# Sprite.net
KiCad netlist of a schematic drawn in EAGLE
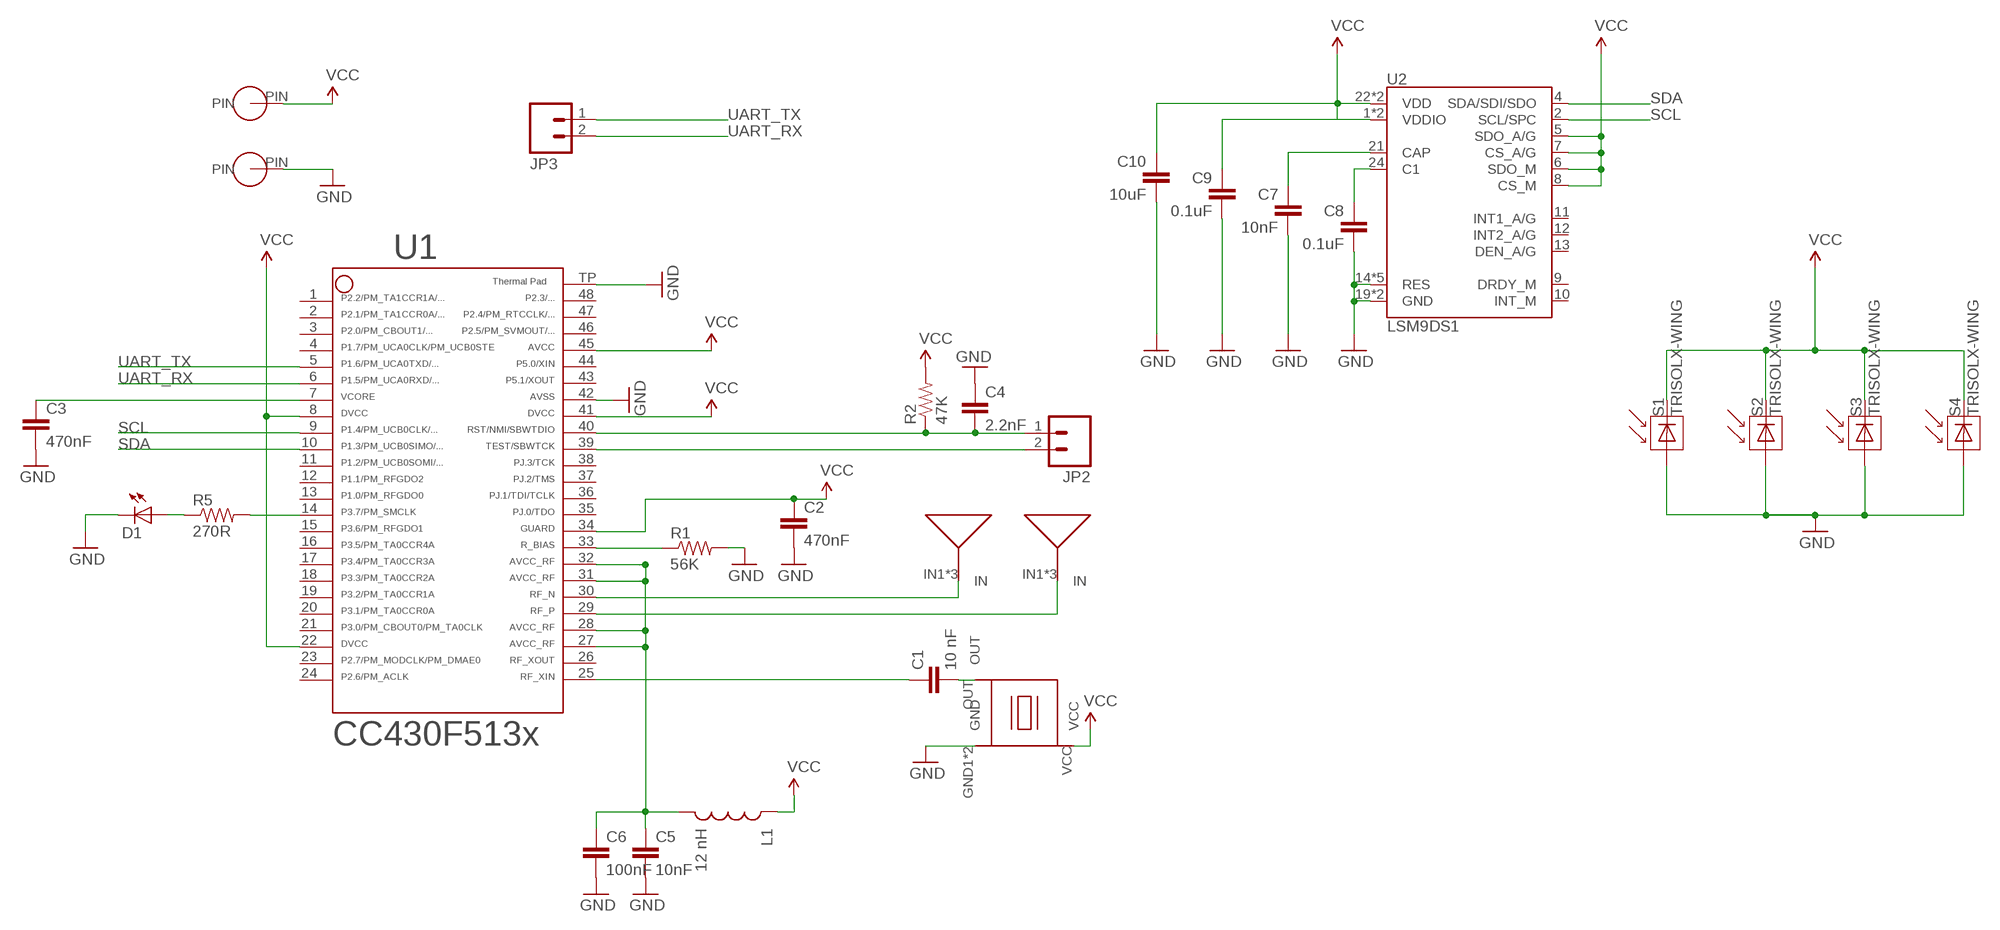
[diagram p0: schematic, sheet 1]

(export (version "E")
  (design (tool "Eeschema 10.0.6"))
  (components
    (comp (ref "ANT-N")
      (value "ANTENNA")
      (footprint "eagle-import:ANTENNA")
      (libsource (lib "eagle-import") (part "ANTENNA"))
    )
    (comp (ref "ANT-P")
      (value "ANTENNA")
      (footprint "eagle-import:ANTENNA")
      (libsource (lib "eagle-import") (part "ANTENNA"))
    )
    (comp (ref "C1")
      (value "10 nF")
      (footprint "eagle-import:0603-CAP")
      (libsource (lib "eagle-import") (part "CAP0603-CAP"))
    )
    (comp (ref "C2")
      (value "470nF")
      (footprint "eagle-import:0603-CAP")
      (libsource (lib "eagle-import") (part "CAP0603-CAP"))
    )
    (comp (ref "C3")
      (value "470nF")
      (footprint "eagle-import:0603-CAP")
      (libsource (lib "eagle-import") (part "CAP0603-CAP"))
    )
    (comp (ref "C4")
      (value "2.2nF")
      (footprint "eagle-import:0603-CAP")
      (libsource (lib "eagle-import") (part "CAP0603-CAP"))
    )
    (comp (ref "C5")
      (value "10nF")
      (footprint "eagle-import:0603-CAP")
      (libsource (lib "eagle-import") (part "CAP0603-CAP"))
    )
    (comp (ref "C6")
      (value "100nF")
      (footprint "eagle-import:0603-CAP")
      (libsource (lib "eagle-import") (part "CAP0603-CAP"))
    )
    (comp (ref "C7")
      (value "10nF")
      (footprint "eagle-import:0603-CAP")
      (libsource (lib "eagle-import") (part "CAP0603-CAP"))
    )
    (comp (ref "C8")
      (value "0.1uF")
      (footprint "eagle-import:0603-CAP")
      (libsource (lib "eagle-import") (part "CAP0603-CAP"))
    )
    (comp (ref "C9")
      (value "0.1uF")
      (footprint "eagle-import:0603-CAP")
      (libsource (lib "eagle-import") (part "CAP0603-CAP"))
    )
    (comp (ref "C10")
      (value "10uF")
      (footprint "eagle-import:0603-CAP")
      (libsource (lib "eagle-import") (part "CAP0603-CAP"))
    )
    (comp (ref "D1")
      (value "LED0603")
      (footprint "eagle-import:LED-0603")
      (libsource (lib "eagle-import") (part "LED0603"))
    )
    (comp (ref "JP2")
      (value "M02PTH")
      (footprint "eagle-import:1X02")
      (libsource (lib "eagle-import") (part "M02PTH"))
    )
    (comp (ref "JP3")
      (value "M02PTH")
      (footprint "eagle-import:1X02")
      (libsource (lib "eagle-import") (part "M02PTH"))
    )
    (comp (ref "L1")
      (value "12 nH")
      (footprint "eagle-import:0603")
      (libsource (lib "eagle-import") (part "INDUCTOR0603"))
    )
    (comp (ref "P1")
      (value "SPRITE_PIN")
      (footprint "eagle-import:SPRITE_PIN")
      (libsource (lib "eagle-import") (part "SPRITE_PIN"))
    )
    (comp (ref "P2")
      (value "SPRITE_PIN")
      (footprint "eagle-import:SPRITE_PIN")
      (libsource (lib "eagle-import") (part "SPRITE_PIN"))
    )
    (comp (ref "R1")
      (value "56K")
      (footprint "eagle-import:0603-RES")
      (libsource (lib "eagle-import") (part "RESISTOR0603-RES"))
    )
    (comp (ref "R2")
      (value "47K")
      (footprint "eagle-import:0603-RES")
      (libsource (lib "eagle-import") (part "RESISTOR0603-RES"))
    )
    (comp (ref "R5")
      (value "270R")
      (footprint "eagle-import:0603-RES")
      (libsource (lib "eagle-import") (part "RESISTOR0603-RES"))
    )
    (comp (ref "S1")
      (value "TRISOLX-WING")
      (footprint "eagle-import:TRISOLX-T01")
      (libsource (lib "eagle-import") (part "TRISOLX-WING"))
    )
    (comp (ref "S2")
      (value "TRISOLX-WING")
      (footprint "eagle-import:TRISOLX-T01")
      (libsource (lib "eagle-import") (part "TRISOLX-WING"))
    )
    (comp (ref "S3")
      (value "TRISOLX-WING")
      (footprint "eagle-import:TRISOLX-T01")
      (libsource (lib "eagle-import") (part "TRISOLX-WING"))
    )
    (comp (ref "S4")
      (value "TRISOLX-WING")
      (footprint "eagle-import:TRISOLX-T01")
      (libsource (lib "eagle-import") (part "TRISOLX-WING"))
    )
    (comp (ref "U1")
      (value "CC430F5137")
      (footprint "eagle-import:RGZ48")
      (libsource (lib "eagle-import") (part "CC430F513X---RGZ48"))
    )
    (comp (ref "U2")
      (value "LSM9DS1")
      (footprint "eagle-import:LGA24-8X4")
      (libsource (lib "eagle-import") (part "LSM9DS1"))
    )
    (comp (ref "X1")
      (value "TCXO_7Z")
      (footprint "eagle-import:TXC_7Z")
      (libsource (lib "eagle-import") (part "TCXO_7Z"))
    )
  )
  (nets
    (net (code "1") (name "GND") (class "Default")
      (node (ref "C10") (pin "2") (pinfunction "2_2") (pintype "passive"))
      (node (ref "C2") (pin "2") (pinfunction "2_2") (pintype "passive"))
      (node (ref "C3") (pin "2") (pinfunction "2_2") (pintype "passive"))
      (node (ref "C4") (pin "1") (pinfunction "1_1") (pintype "passive"))
      (node (ref "C5") (pin "2") (pinfunction "2_2") (pintype "passive"))
      (node (ref "C6") (pin "2") (pinfunction "2_2") (pintype "passive"))
      (node (ref "C7") (pin "2") (pinfunction "2_2") (pintype "passive"))
      (node (ref "C8") (pin "2") (pinfunction "2_2") (pintype "passive"))
      (node (ref "C9") (pin "2") (pinfunction "2_2") (pintype "passive"))
      (node (ref "D1") (pin "C") (pinfunction "C_C") (pintype "passive"))
      (node (ref "P1") (pin "PIN") (pinfunction "PIN_PIN") (pintype "bidirectional"))
      (node (ref "R1") (pin "2") (pinfunction "2_2") (pintype "passive"))
      (node (ref "S1") (pin "P$3") (pinfunction "A_P$3") (pintype "passive"))
      (node (ref "S2") (pin "P$3") (pinfunction "A_P$3") (pintype "passive"))
      (node (ref "S3") (pin "P$3") (pinfunction "A_P$3") (pintype "passive"))
      (node (ref "S4") (pin "P$3") (pinfunction "A_P$3") (pintype "passive"))
      (node (ref "U1") (pin "42") (pinfunction "42_42") (pintype "power_in"))
      (node (ref "U1") (pin "TP") (pinfunction "49_TP") (pintype "power_in"))
      (node (ref "U2") (pin "14") (pinfunction "RES_14") (pintype "bidirectional"))
      (node (ref "U2") (pin "15") (pinfunction "RES_15") (pintype "bidirectional"))
      (node (ref "U2") (pin "16") (pinfunction "RES_16") (pintype "bidirectional"))
      (node (ref "U2") (pin "17") (pinfunction "RES_17") (pintype "bidirectional"))
      (node (ref "U2") (pin "18") (pinfunction "RES_18") (pintype "bidirectional"))
      (node (ref "U2") (pin "19") (pinfunction "GND_19") (pintype "bidirectional"))
      (node (ref "U2") (pin "20") (pinfunction "GND_20") (pintype "bidirectional"))
      (node (ref "X1") (pin "GND1") (pinfunction "GND_GND1") (pintype "bidirectional"))
      (node (ref "X1") (pin "GND2") (pinfunction "GND_GND2") (pintype "bidirectional"))
    )
    (net (code "2") (name "Net-(ANT-N-IN-PadIN1)") (class "Default")
      (node (ref "ANT-N") (pin "IN1") (pinfunction "IN_IN1") (pintype "bidirectional"))
      (node (ref "ANT-N") (pin "IN2") (pinfunction "IN_IN2") (pintype "bidirectional"))
      (node (ref "ANT-N") (pin "IN3") (pinfunction "IN_IN3") (pintype "bidirectional"))
      (node (ref "U1") (pin "30") (pinfunction "30_30") (pintype "bidirectional"))
    )
    (net (code "3") (name "Net-(ANT-P-IN-PadIN1)") (class "Default")
      (node (ref "ANT-P") (pin "IN1") (pinfunction "IN_IN1") (pintype "bidirectional"))
      (node (ref "ANT-P") (pin "IN2") (pinfunction "IN_IN2") (pintype "bidirectional"))
      (node (ref "ANT-P") (pin "IN3") (pinfunction "IN_IN3") (pintype "bidirectional"))
      (node (ref "U1") (pin "29") (pinfunction "29_29") (pintype "bidirectional"))
    )
    (net (code "4") (name "Net-(C1-Pad1)") (class "Default")
      (node (ref "C1") (pin "1") (pinfunction "1_1") (pintype "passive"))
      (node (ref "U1") (pin "25") (pinfunction "25_25") (pintype "input"))
    )
    (net (code "5") (name "Net-(C1-Pad2)") (class "Default")
      (node (ref "C1") (pin "2") (pinfunction "2_2") (pintype "passive"))
      (node (ref "X1") (pin "OUT") (pinfunction "OUT_OUT") (pintype "bidirectional"))
    )
    (net (code "6") (name "Net-(C3-Pad1)") (class "Default")
      (node (ref "C3") (pin "1") (pinfunction "1_1") (pintype "passive"))
      (node (ref "U1") (pin "7") (pinfunction "7_7") (pintype "power_in"))
    )
    (net (code "7") (name "Net-(C4-Pad2)") (class "Default")
      (node (ref "C4") (pin "2") (pinfunction "2_2") (pintype "passive"))
      (node (ref "JP2") (pin "1") (pinfunction "1_1") (pintype "passive"))
      (node (ref "R2") (pin "1") (pinfunction "1_1") (pintype "passive"))
      (node (ref "U1") (pin "40") (pinfunction "40_40") (pintype "bidirectional"))
    )
    (net (code "8") (name "Net-(C5-Pad1)") (class "Default")
      (node (ref "C5") (pin "1") (pinfunction "1_1") (pintype "passive"))
      (node (ref "C6") (pin "1") (pinfunction "1_1") (pintype "passive"))
      (node (ref "L1") (pin "2") (pinfunction "2_2") (pintype "passive"))
      (node (ref "U1") (pin "27") (pinfunction "27_27") (pintype "power_in"))
      (node (ref "U1") (pin "28") (pinfunction "28_28") (pintype "bidirectional"))
      (node (ref "U1") (pin "31") (pinfunction "31_31") (pintype "power_in"))
      (node (ref "U1") (pin "32") (pinfunction "32_32") (pintype "power_in"))
    )
    (net (code "9") (name "Net-(D1-PadA)") (class "Default")
      (node (ref "D1") (pin "A") (pinfunction "A_A") (pintype "passive"))
      (node (ref "R5") (pin "1") (pinfunction "1_1") (pintype "passive"))
    )
    (net (code "10") (name "Net-(JP2-Pad2)") (class "Default")
      (node (ref "JP2") (pin "2") (pinfunction "2_2") (pintype "passive"))
      (node (ref "U1") (pin "39") (pinfunction "39_39") (pintype "input"))
    )
    (net (code "11") (name "Net-(R1-Pad1)") (class "Default")
      (node (ref "R1") (pin "1") (pinfunction "1_1") (pintype "passive"))
      (node (ref "U1") (pin "33") (pinfunction "33_33") (pintype "power_in"))
    )
    (net (code "12") (name "Net-(R5-Pad2)") (class "Default")
      (node (ref "R5") (pin "2") (pinfunction "2_2") (pintype "passive"))
      (node (ref "U1") (pin "14") (pinfunction "14_14") (pintype "bidirectional"))
    )
    (net (code "13") (name "Net-(U2-C1)") (class "Default")
      (node (ref "C8") (pin "1") (pinfunction "1_1") (pintype "passive"))
      (node (ref "U2") (pin "24") (pinfunction "C1_24") (pintype "bidirectional"))
    )
    (net (code "14") (name "Net-(U2-CAP)") (class "Default")
      (node (ref "C7") (pin "1") (pinfunction "1_1") (pintype "passive"))
      (node (ref "U2") (pin "21") (pinfunction "CAP_21") (pintype "bidirectional"))
    )
    (net (code "15") (name "SCL") (class "Default")
      (node (ref "U1") (pin "9") (pinfunction "9_9") (pintype "bidirectional"))
      (node (ref "U2") (pin "2") (pinfunction "SCL/SPC_2") (pintype "bidirectional"))
    )
    (net (code "16") (name "SDA") (class "Default")
      (node (ref "U1") (pin "10") (pinfunction "10_10") (pintype "bidirectional"))
      (node (ref "U2") (pin "4") (pinfunction "SDA/SDI/SDO_4") (pintype "bidirectional"))
    )
    (net (code "17") (name "UART_RX") (class "Default")
      (node (ref "JP3") (pin "2") (pinfunction "2_2") (pintype "passive"))
      (node (ref "U1") (pin "6") (pinfunction "6_6") (pintype "bidirectional"))
    )
    (net (code "18") (name "UART_TX") (class "Default")
      (node (ref "JP3") (pin "1") (pinfunction "1_1") (pintype "passive"))
      (node (ref "U1") (pin "5") (pinfunction "5_5") (pintype "bidirectional"))
    )
    (net (code "19") (name "VCC") (class "Default")
      (node (ref "C10") (pin "1") (pinfunction "1_1") (pintype "passive"))
      (node (ref "C2") (pin "1") (pinfunction "1_1") (pintype "passive"))
      (node (ref "C9") (pin "1") (pinfunction "1_1") (pintype "passive"))
      (node (ref "L1") (pin "1") (pinfunction "1_1") (pintype "passive"))
      (node (ref "P2") (pin "PIN") (pinfunction "PIN_PIN") (pintype "bidirectional"))
      (node (ref "R2") (pin "2") (pinfunction "2_2") (pintype "passive"))
      (node (ref "S1") (pin "P$2") (pinfunction "C_P$2") (pintype "passive"))
      (node (ref "S2") (pin "P$2") (pinfunction "C_P$2") (pintype "passive"))
      (node (ref "S3") (pin "P$2") (pinfunction "C_P$2") (pintype "passive"))
      (node (ref "S4") (pin "P$2") (pinfunction "C_P$2") (pintype "passive"))
      (node (ref "U1") (pin "22") (pinfunction "22_22") (pintype "power_in"))
      (node (ref "U1") (pin "34") (pinfunction "34_34") (pintype "power_in"))
      (node (ref "U1") (pin "41") (pinfunction "41_41") (pintype "power_in"))
      (node (ref "U1") (pin "45") (pinfunction "45_45") (pintype "input"))
      (node (ref "U1") (pin "8") (pinfunction "8_8") (pintype "power_in"))
      (node (ref "U2") (pin "1") (pinfunction "VDDIO_1") (pintype "bidirectional"))
      (node (ref "U2") (pin "22") (pinfunction "VDD_22") (pintype "bidirectional"))
      (node (ref "U2") (pin "23") (pinfunction "VDD_23") (pintype "bidirectional"))
      (node (ref "U2") (pin "3") (pinfunction "VDDIO_3") (pintype "bidirectional"))
      (node (ref "U2") (pin "5") (pinfunction "SDO_A/G_5") (pintype "bidirectional"))
      (node (ref "U2") (pin "6") (pinfunction "SDO_M_6") (pintype "bidirectional"))
      (node (ref "U2") (pin "7") (pinfunction "CS_A/G_7") (pintype "bidirectional"))
      (node (ref "U2") (pin "8") (pinfunction "CS_M_8") (pintype "bidirectional"))
      (node (ref "X1") (pin "VCC") (pinfunction "VCC_VCC") (pintype "bidirectional"))
    )
    (net (code "20") (name "unconnected-(U1-Pad1)") (class "Default")
      (node (ref "U1") (pin "1") (pinfunction "1_1") (pintype "bidirectional"))
    )
    (net (code "21") (name "unconnected-(U1-Pad2)") (class "Default")
      (node (ref "U1") (pin "2") (pinfunction "2_2") (pintype "bidirectional"))
    )
    (net (code "22") (name "unconnected-(U1-Pad3)") (class "Default")
      (node (ref "U1") (pin "3") (pinfunction "3_3") (pintype "bidirectional"))
    )
    (net (code "23") (name "unconnected-(U1-Pad4)") (class "Default")
      (node (ref "U1") (pin "4") (pinfunction "4_4") (pintype "bidirectional"))
    )
    (net (code "24") (name "unconnected-(U1-Pad11)") (class "Default")
      (node (ref "U1") (pin "11") (pinfunction "11_11") (pintype "bidirectional"))
    )
    (net (code "25") (name "unconnected-(U1-Pad12)") (class "Default")
      (node (ref "U1") (pin "12") (pinfunction "12_12") (pintype "bidirectional"))
    )
    (net (code "26") (name "unconnected-(U1-Pad13)") (class "Default")
      (node (ref "U1") (pin "13") (pinfunction "13_13") (pintype "bidirectional"))
    )
    (net (code "27") (name "unconnected-(U1-Pad15)") (class "Default")
      (node (ref "U1") (pin "15") (pinfunction "15_15") (pintype "bidirectional"))
    )
    (net (code "28") (name "unconnected-(U1-Pad16)") (class "Default")
      (node (ref "U1") (pin "16") (pinfunction "16_16") (pintype "bidirectional"))
    )
    (net (code "29") (name "unconnected-(U1-Pad17)") (class "Default")
      (node (ref "U1") (pin "17") (pinfunction "17_17") (pintype "bidirectional"))
    )
    (net (code "30") (name "unconnected-(U1-Pad18)") (class "Default")
      (node (ref "U1") (pin "18") (pinfunction "18_18") (pintype "bidirectional"))
    )
    (net (code "31") (name "unconnected-(U1-Pad19)") (class "Default")
      (node (ref "U1") (pin "19") (pinfunction "19_19") (pintype "bidirectional"))
    )
    (net (code "32") (name "unconnected-(U1-Pad20)") (class "Default")
      (node (ref "U1") (pin "20") (pinfunction "20_20") (pintype "bidirectional"))
    )
    (net (code "33") (name "unconnected-(U1-Pad21)") (class "Default")
      (node (ref "U1") (pin "21") (pinfunction "21_21") (pintype "bidirectional"))
    )
    (net (code "34") (name "unconnected-(U1-Pad23)") (class "Default")
      (node (ref "U1") (pin "23") (pinfunction "23_23") (pintype "bidirectional"))
    )
    (net (code "35") (name "unconnected-(U1-Pad24)") (class "Default")
      (node (ref "U1") (pin "24") (pinfunction "24_24") (pintype "bidirectional"))
    )
    (net (code "36") (name "unconnected-(U1-Pad26)") (class "Default")
      (node (ref "U1") (pin "26") (pinfunction "26_26") (pintype "output"))
    )
    (net (code "37") (name "unconnected-(U1-Pad35)") (class "Default")
      (node (ref "U1") (pin "35") (pinfunction "35_35") (pintype "bidirectional"))
    )
    (net (code "38") (name "unconnected-(U1-Pad36)") (class "Default")
      (node (ref "U1") (pin "36") (pinfunction "36_36") (pintype "bidirectional"))
    )
    (net (code "39") (name "unconnected-(U1-Pad37)") (class "Default")
      (node (ref "U1") (pin "37") (pinfunction "37_37") (pintype "bidirectional"))
    )
    (net (code "40") (name "unconnected-(U1-Pad38)") (class "Default")
      (node (ref "U1") (pin "38") (pinfunction "38_38") (pintype "bidirectional"))
    )
    (net (code "41") (name "unconnected-(U1-Pad43)") (class "Default")
      (node (ref "U1") (pin "43") (pinfunction "43_43") (pintype "input"))
    )
    (net (code "42") (name "unconnected-(U1-Pad44)") (class "Default")
      (node (ref "U1") (pin "44") (pinfunction "44_44") (pintype "input"))
    )
    (net (code "43") (name "unconnected-(U1-Pad46)") (class "Default")
      (node (ref "U1") (pin "46") (pinfunction "46_46") (pintype "bidirectional"))
    )
    (net (code "44") (name "unconnected-(U1-Pad47)") (class "Default")
      (node (ref "U1") (pin "47") (pinfunction "47_47") (pintype "input"))
    )
    (net (code "45") (name "unconnected-(U1-Pad48)") (class "Default")
      (node (ref "U1") (pin "48") (pinfunction "48_48") (pintype "bidirectional"))
    )
    (net (code "46") (name "unconnected-(U2-DEN_A{slash}G-Pad13)") (class "Default")
      (node (ref "U2") (pin "13") (pinfunction "DEN_A/G_13") (pintype "bidirectional"))
    )
    (net (code "47") (name "unconnected-(U2-DRDY_M-Pad9)") (class "Default")
      (node (ref "U2") (pin "9") (pinfunction "DRDY_M_9") (pintype "bidirectional"))
    )
    (net (code "48") (name "unconnected-(U2-INT1_A{slash}G-Pad11)") (class "Default")
      (node (ref "U2") (pin "11") (pinfunction "INT1_A/G_11") (pintype "bidirectional"))
    )
    (net (code "49") (name "unconnected-(U2-INT2_A{slash}G-Pad12)") (class "Default")
      (node (ref "U2") (pin "12") (pinfunction "INT2_A/G_12") (pintype "bidirectional"))
    )
    (net (code "50") (name "unconnected-(U2-INT_M-Pad10)") (class "Default")
      (node (ref "U2") (pin "10") (pinfunction "INT_M_10") (pintype "bidirectional"))
    )
  )
)
